# v2_hackspace.net
KiCad netlist of a schematic drawn in EAGLE
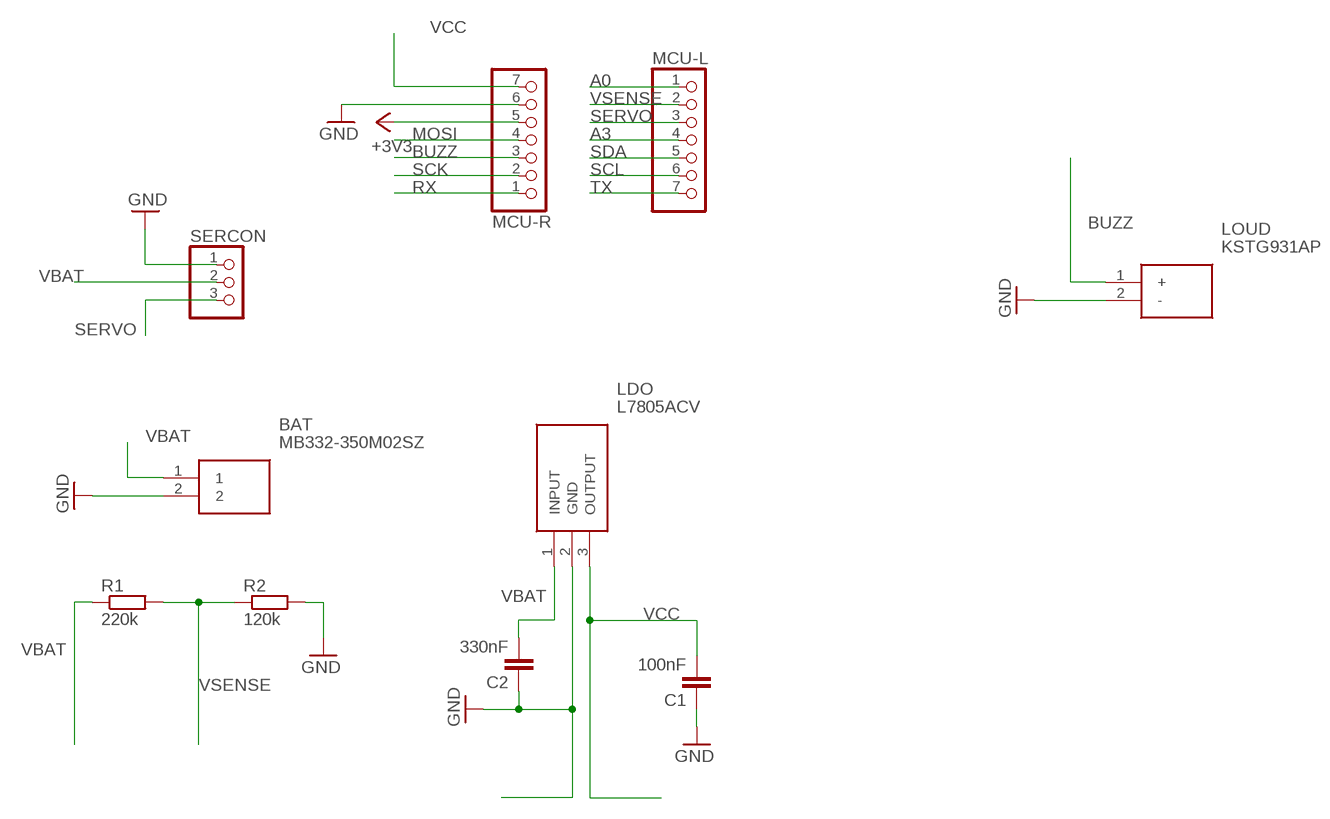
[diagram p0: schematic, sheet 1]

(export (version "E")
  (design (tool "Eeschema 10.0.6"))
  (components
    (comp (ref "BAT")
      (value "MB332-350M02SZ")
      (footprint "eagle-import:MB332350M02SZ")
      (fields (field (name "RS_PART_NUMBER") "7901149"))
      (libsource (lib "eagle-import") (part "MB332-350M02SZ"))
    )
    (comp (ref "C1")
      (value "100nF")
      (footprint "eagle-import:C025-024X044")
      (libsource (lib "eagle-import") (part "C-EU025-024X044"))
    )
    (comp (ref "C2")
      (value "330nF")
      (footprint "eagle-import:C025-024X044")
      (libsource (lib "eagle-import") (part "C-EU025-024X044"))
    )
    (comp (ref "LDO")
      (value "L7805ACV")
      (footprint "eagle-import:TO255P460X1020X2008-3P")
      (fields (field (name "RS_PART_NUMBER") "2988508P"))
      (libsource (lib "eagle-import") (part "L7805ACV"))
    )
    (comp (ref "LOUD")
      (value "KSTG931AP")
      (footprint "eagle-import:CAPPRD400W70D900H500")
      (libsource (lib "eagle-import") (part "KSTG931AP"))
    )
    (comp (ref "MCU-L")
      (value "HEADER-1X7")
      (footprint "eagle-import:1X07_OVAL")
      (libsource (lib "eagle-import") (part "HEADER-1X7"))
    )
    (comp (ref "MCU-R")
      (value "HEADER-1X7")
      (footprint "eagle-import:1X07_OVAL")
      (libsource (lib "eagle-import") (part "HEADER-1X7"))
    )
    (comp (ref "R1")
      (value "220k")
      (footprint "eagle-import:0204V")
      (libsource (lib "eagle-import") (part "R-EU_0204/2V"))
    )
    (comp (ref "R2")
      (value "120k")
      (footprint "eagle-import:0204V")
      (libsource (lib "eagle-import") (part "R-EU_0204/2V"))
    )
    (comp (ref "SERCON")
      (value "PINHD-1X3")
      (footprint "eagle-import:1X03")
      (libsource (lib "eagle-import") (part "PINHD-1X3"))
    )
  )
  (nets
    (net (code "1") (name "+3V3") (class "Default")
      (node (ref "MCU-R") (pin "5") (pinfunction "5_5") (pintype "passive"))
    )
    (net (code "2") (name "/A0") (class "Default")
      (node (ref "MCU-L") (pin "1") (pinfunction "1_1") (pintype "passive"))
    )
    (net (code "3") (name "/A3") (class "Default")
      (node (ref "MCU-L") (pin "4") (pinfunction "4_4") (pintype "passive"))
    )
    (net (code "4") (name "/BUZZ") (class "Default")
      (node (ref "LOUD") (pin "1") (pinfunction "+_1") (pintype "bidirectional"))
      (node (ref "MCU-R") (pin "3") (pinfunction "3_3") (pintype "passive"))
    )
    (net (code "5") (name "/MOSI") (class "Default")
      (node (ref "MCU-R") (pin "4") (pinfunction "4_4") (pintype "passive"))
    )
    (net (code "6") (name "/RX") (class "Default")
      (node (ref "MCU-R") (pin "1") (pinfunction "1_1") (pintype "passive"))
    )
    (net (code "7") (name "/SCK") (class "Default")
      (node (ref "MCU-R") (pin "2") (pinfunction "2_2") (pintype "passive"))
    )
    (net (code "8") (name "/SCL") (class "Default")
      (node (ref "MCU-L") (pin "6") (pinfunction "6_6") (pintype "passive"))
    )
    (net (code "9") (name "/SDA") (class "Default")
      (node (ref "MCU-L") (pin "5") (pinfunction "5_5") (pintype "passive"))
    )
    (net (code "10") (name "/SERVO") (class "Default")
      (node (ref "MCU-L") (pin "3") (pinfunction "3_3") (pintype "passive"))
      (node (ref "SERCON") (pin "3") (pinfunction "3_3") (pintype "passive"))
    )
    (net (code "11") (name "/TX") (class "Default")
      (node (ref "MCU-L") (pin "7") (pinfunction "7_7") (pintype "passive"))
    )
    (net (code "12") (name "/VBAT") (class "Default")
      (node (ref "BAT") (pin "1") (pinfunction "1_1") (pintype "bidirectional"))
      (node (ref "C2") (pin "2") (pinfunction "2_2") (pintype "passive"))
      (node (ref "LDO") (pin "1") (pinfunction "INPUT_1") (pintype "bidirectional"))
      (node (ref "R1") (pin "1") (pinfunction "1_1") (pintype "passive"))
      (node (ref "SERCON") (pin "2") (pinfunction "2_2") (pintype "passive"))
    )
    (net (code "13") (name "/VCC") (class "Default")
      (node (ref "C1") (pin "2") (pinfunction "2_2") (pintype "passive"))
      (node (ref "LDO") (pin "3") (pinfunction "OUTPUT_3") (pintype "bidirectional"))
      (node (ref "MCU-R") (pin "7") (pinfunction "7_7") (pintype "passive"))
    )
    (net (code "14") (name "/VSENSE") (class "Default")
      (node (ref "MCU-L") (pin "2") (pinfunction "2_2") (pintype "passive"))
      (node (ref "R1") (pin "2") (pinfunction "2_2") (pintype "passive"))
      (node (ref "R2") (pin "1") (pinfunction "1_1") (pintype "passive"))
    )
    (net (code "15") (name "GND") (class "Default")
      (node (ref "BAT") (pin "2") (pinfunction "2_2") (pintype "bidirectional"))
      (node (ref "C1") (pin "1") (pinfunction "1_1") (pintype "passive"))
      (node (ref "C2") (pin "1") (pinfunction "1_1") (pintype "passive"))
      (node (ref "LDO") (pin "2") (pinfunction "GND_2") (pintype "bidirectional"))
      (node (ref "LOUD") (pin "2") (pinfunction "-_2") (pintype "bidirectional"))
      (node (ref "MCU-R") (pin "6") (pinfunction "6_6") (pintype "passive"))
      (node (ref "R2") (pin "2") (pinfunction "2_2") (pintype "passive"))
      (node (ref "SERCON") (pin "1") (pinfunction "1_1") (pintype "passive"))
    )
  )
)
